# LHC.net
KiCad netlist of a schematic drawn in Altium Designer
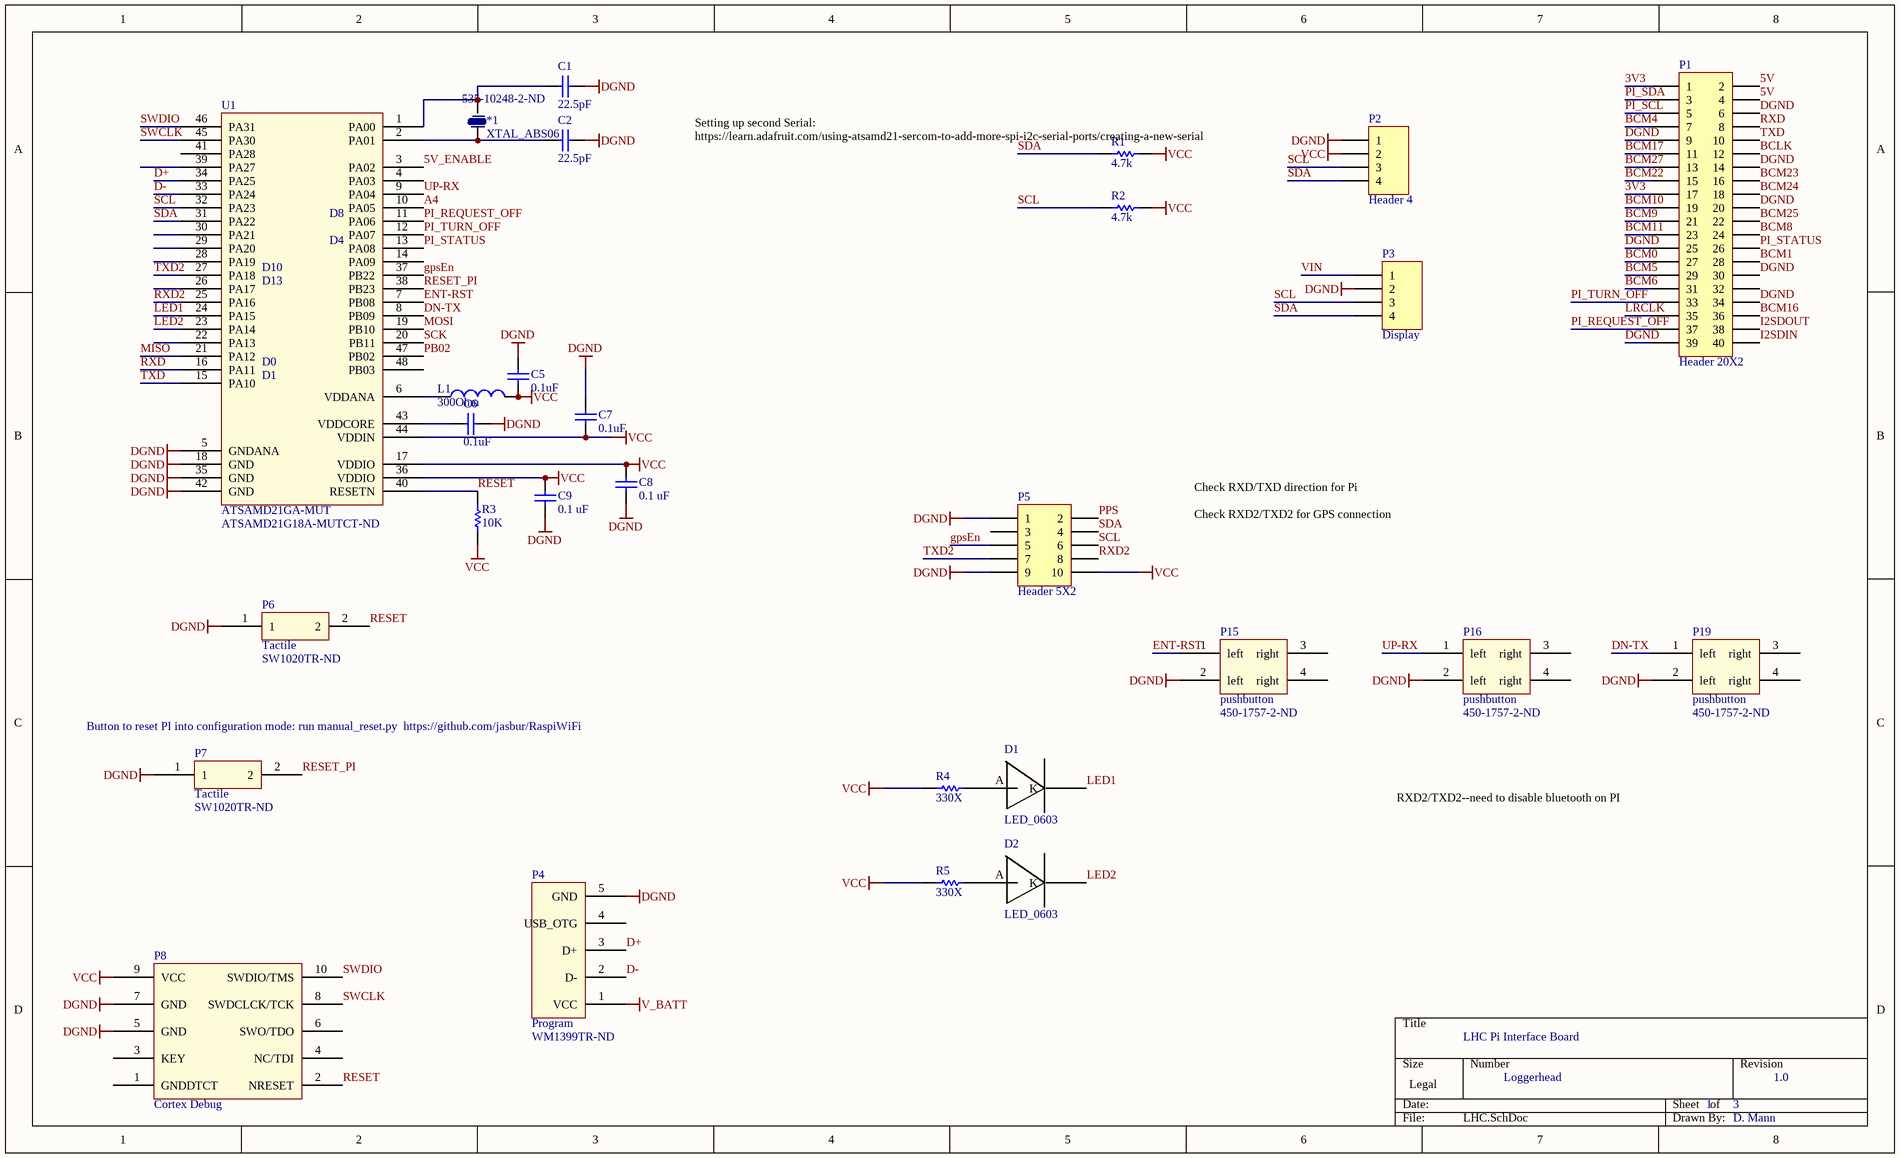
[diagram p0: LHC.SchDoc]

(export (version "E")
  (design (tool "Eeschema 10.0.6"))
  (components
    (comp (ref "*1")
      (value "XTAL_ABS06")
      (footprint "XTAL-ABS06")
      (fields (field (name "SUPPLIER PART NUMBER 1") "535-10248-2-ND"))
      (libsource (lib "Loggerhead") (part "XTAL_ABS06"))
    )
    (comp (ref "C1")
      (value "22.5pF")
      (footprint "0402")
      (description "Ceramic Chip Capacitor - Standard")
      (fields (field (name "PUBLISHER") "Altium Limited"))
      (libsource (lib "KEMET Chip Capacitor") (part "C0402"))
    )
    (comp (ref "C2")
      (value "22.5pF")
      (footprint "0402")
      (description "Ceramic Chip Capacitor - Standard")
      (fields (field (name "PUBLISHER") "Altium Limited"))
      (libsource (lib "KEMET Chip Capacitor") (part "C0402"))
    )
    (comp (ref "C5")
      (value "0.1uF")
      (footprint "0402")
      (description "Ceramic Chip Capacitor - Standard")
      (fields (field (name "PUBLISHER") "Altium Limited"))
      (libsource (lib "KEMET Chip Capacitor") (part "C0402"))
    )
    (comp (ref "C6")
      (value "0.1uF")
      (footprint "0402")
      (description "Ceramic Chip Capacitor - Standard")
      (fields (field (name "PUBLISHER") "Altium Limited"))
      (libsource (lib "KEMET Chip Capacitor") (part "C0402"))
    )
    (comp (ref "C7")
      (value "0.1uF")
      (footprint "0402")
      (description "Ceramic Chip Capacitor - Standard")
      (fields (field (name "PUBLISHER") "Altium Limited"))
      (libsource (lib "KEMET Chip Capacitor") (part "C0402"))
    )
    (comp (ref "C8")
      (value "0.1 uF")
      (footprint "0402")
      (description "Ceramic Chip Capacitor - Standard")
      (fields (field (name "PUBLISHER") "Altium Limited"))
      (libsource (lib "KEMET Chip Capacitor") (part "C0402"))
    )
    (comp (ref "C9")
      (value "0.1 uF")
      (footprint "0402")
      (description "Ceramic Chip Capacitor - Standard")
      (fields (field (name "PUBLISHER") "Altium Limited"))
      (libsource (lib "KEMET Chip Capacitor") (part "C0402"))
    )
    (comp (ref "D1")
      (value "LED_0603")
      (footprint "Diode0603")
      (libsource (lib "Loggerhead") (part "LED_0603"))
    )
    (comp (ref "D2")
      (value "LED_0603")
      (footprint "Diode0603")
      (libsource (lib "Loggerhead") (part "LED_0603"))
    )
    (comp (ref "L1")
      (value "300Ohm")
      (footprint "0805 (M2125) Ferrite")
      (description "Ferrite 25mOhm@DC,  60 Ohm@100MHz")
      (fields
        (field (name "CREATOR AND DATE") "Design Engineer's Name")
        (field (name "FOOTPRINT VERIFIED BY") "*")
        (field (name "SCHEMATIC VERIFIED BY") "*")
        (field (name "VENDOR INFO VERIFIED BY") "*")
      )
      (libsource (lib "Flanery") (part "Ferrite 0805(M2125) 3A"))
    )
    (comp (ref "P1")
      (value "Header 20X2")
      (footprint "HDR2X20")
      (description "Header, 20-Pin, Dual row")
      (fields (field (name "PUBLISHER") "Altium Limited"))
      (libsource (lib "Miscellaneous Connectors") (part "Header 20X2"))
    )
    (comp (ref "P2")
      (value "Header 4")
      (footprint "HDR1X4")
      (description "Header, 4-Pin")
      (fields (field (name "PUBLISHER") "Altium Limited"))
      (libsource (lib "Miscellaneous Connectors") (part "Header 4"))
    )
    (comp (ref "P3")
      (value "Display")
      (footprint "HDR1X4")
      (description "Header, 4-Pin")
      (fields (field (name "PUBLISHER") "Altium Limited"))
      (libsource (lib "Miscellaneous Connectors") (part "Header 4"))
    )
    (comp (ref "P4")
      (value "Program")
      (footprint "microUSB-B")
      (fields (field (name "SUPPLIER PART NUMBER 1") "WM1399TR-ND"))
      (libsource (lib "Loggerhead") (part "microUSB-B"))
    )
    (comp (ref "P5")
      (value "Header 5X2")
      (footprint "HDR2X5")
      (description "Header, 5-Pin, Dual row")
      (fields (field (name "PUBLISHER") "Altium Limited"))
      (libsource (lib "Miscellaneous Connectors") (part "Header 5X2"))
    )
    (comp (ref "P6")
      (value "Tactile")
      (footprint "Tactile-B3U-1000")
      (fields (field (name "SUPPLIER PART NUMBER 1") "SW1020TR-ND"))
      (libsource (lib "Loggerhead") (part "Tactile_B3U-1000"))
    )
    (comp (ref "P7")
      (value "Tactile")
      (footprint "Tactile-B3U-1000")
      (fields (field (name "SUPPLIER PART NUMBER 1") "SW1020TR-ND"))
      (libsource (lib "Loggerhead") (part "Tactile_B3U-1000"))
    )
    (comp (ref "P8")
      (value "Cortex Debug")
      (footprint "Header_2x5_50mil")
      (libsource (lib "Loggerhead") (part "CortexDebug"))
    )
    (comp (ref "P15")
      (value "pushbutton")
      (footprint "SOP4")
      (fields (field (name "SUPPLIER PART NUMBER 1") "450-1757-2-ND"))
      (libsource (lib "Loggerhead") (part "pushbutton"))
    )
    (comp (ref "P16")
      (value "pushbutton")
      (footprint "SOP4")
      (fields (field (name "SUPPLIER PART NUMBER 1") "450-1757-2-ND"))
      (libsource (lib "Loggerhead") (part "pushbutton"))
    )
    (comp (ref "P19")
      (value "pushbutton")
      (footprint "SOP4")
      (fields (field (name "SUPPLIER PART NUMBER 1") "450-1757-2-ND"))
      (libsource (lib "Loggerhead") (part "pushbutton"))
    )
    (comp (ref "R1")
      (value "4.7k")
      (footprint "3-0603")
      (fields (field (name "PUBLISHER") "Altium Limited"))
      (libsource (lib "Panasonic Resistor") (part "ERJ3RK"))
    )
    (comp (ref "R2")
      (value "4.7k")
      (footprint "3-0603")
      (fields (field (name "PUBLISHER") "Altium Limited"))
      (libsource (lib "Panasonic Resistor") (part "ERJ3RK"))
    )
    (comp (ref "R3")
      (value "10K")
      (footprint "3-0603")
      (fields (field (name "PUBLISHER") "Altium Limited"))
      (libsource (lib "Panasonic Resistor") (part "ERJ3RK"))
    )
    (comp (ref "R4")
      (value "330X")
      (footprint "3-0603")
      (fields (field (name "PUBLISHER") "Altium Limited"))
      (libsource (lib "Panasonic Resistor") (part "ERJ3RK"))
    )
    (comp (ref "R5")
      (value "330X")
      (footprint "3-0603")
      (fields (field (name "PUBLISHER") "Altium Limited"))
      (libsource (lib "Panasonic Resistor") (part "ERJ3RK"))
    )
    (comp (ref "U1")
      (value "ATSAMD21GA-MUT")
      (footprint "QFN127P600-8N")
      (fields (field (name "SUPPLIER PART NUMBER 1") "ATSAMD21G18A-MUTCT-ND"))
      (libsource (lib "Loggerhead") (part "ATSAMD21G18"))
    )
  )
  (nets
    (net (code "1") (name "/3V3") (class "Default")
      (node (ref "P1") (pin "1") (pinfunction "1_1") (pintype "passive"))
      (node (ref "P1") (pin "17") (pinfunction "17_17") (pintype "passive"))
    )
    (net (code "2") (name "/5V") (class "Default")
      (node (ref "P1") (pin "2") (pinfunction "2_2") (pintype "passive"))
      (node (ref "P1") (pin "4") (pinfunction "4_4") (pintype "passive"))
    )
    (net (code "3") (name "/5V_ENABLE") (class "Default")
      (node (ref "U1") (pin "3") (pinfunction "PA02_3") (pintype "passive"))
    )
    (net (code "4") (name "/A4") (class "Default")
      (node (ref "U1") (pin "10") (pinfunction "PA05_10") (pintype "passive"))
    )
    (net (code "5") (name "/BCLK") (class "Default")
      (node (ref "P1") (pin "12") (pinfunction "12_12") (pintype "passive"))
    )
    (net (code "6") (name "/BCM0") (class "Default")
      (node (ref "P1") (pin "27") (pinfunction "27_27") (pintype "passive"))
    )
    (net (code "7") (name "/BCM1") (class "Default")
      (node (ref "P1") (pin "28") (pinfunction "28_28") (pintype "passive"))
    )
    (net (code "8") (name "/BCM4") (class "Default")
      (node (ref "P1") (pin "7") (pinfunction "7_7") (pintype "passive"))
    )
    (net (code "9") (name "/BCM5") (class "Default")
      (node (ref "P1") (pin "29") (pinfunction "29_29") (pintype "passive"))
    )
    (net (code "10") (name "/BCM6") (class "Default")
      (node (ref "P1") (pin "31") (pinfunction "31_31") (pintype "passive"))
    )
    (net (code "11") (name "/BCM8") (class "Default")
      (node (ref "P1") (pin "24") (pinfunction "24_24") (pintype "passive"))
    )
    (net (code "12") (name "/BCM9") (class "Default")
      (node (ref "P1") (pin "21") (pinfunction "21_21") (pintype "passive"))
    )
    (net (code "13") (name "/BCM10") (class "Default")
      (node (ref "P1") (pin "19") (pinfunction "19_19") (pintype "passive"))
    )
    (net (code "14") (name "/BCM11") (class "Default")
      (node (ref "P1") (pin "23") (pinfunction "23_23") (pintype "passive"))
    )
    (net (code "15") (name "/BCM16") (class "Default")
      (node (ref "P1") (pin "36") (pinfunction "36_36") (pintype "passive"))
    )
    (net (code "16") (name "/BCM17") (class "Default")
      (node (ref "P1") (pin "11") (pinfunction "11_11") (pintype "passive"))
    )
    (net (code "17") (name "/BCM22") (class "Default")
      (node (ref "P1") (pin "15") (pinfunction "15_15") (pintype "passive"))
    )
    (net (code "18") (name "/BCM23") (class "Default")
      (node (ref "P1") (pin "16") (pinfunction "16_16") (pintype "passive"))
    )
    (net (code "19") (name "/BCM24") (class "Default")
      (node (ref "P1") (pin "18") (pinfunction "18_18") (pintype "passive"))
    )
    (net (code "20") (name "/BCM25") (class "Default")
      (node (ref "P1") (pin "22") (pinfunction "22_22") (pintype "passive"))
    )
    (net (code "21") (name "/BCM27") (class "Default")
      (node (ref "P1") (pin "13") (pinfunction "13_13") (pintype "passive"))
    )
    (net (code "22") (name "/D+") (class "Default")
      (node (ref "P4") (pin "3") (pinfunction "D+_3") (pintype "passive"))
      (node (ref "U1") (pin "34") (pinfunction "PA25_34") (pintype "passive"))
    )
    (net (code "23") (name "/D-") (class "Default")
      (node (ref "P4") (pin "2") (pinfunction "D-_2") (pintype "passive"))
      (node (ref "U1") (pin "33") (pinfunction "PA24_33") (pintype "passive"))
    )
    (net (code "24") (name "/DN-TX") (class "Default")
      (node (ref "P19") (pin "1") (pinfunction "left_1") (pintype "passive"))
      (node (ref "U1") (pin "8") (pinfunction "PB09_8") (pintype "passive"))
    )
    (net (code "25") (name "/ENT-RST") (class "Default")
      (node (ref "P15") (pin "1") (pinfunction "left_1") (pintype "passive"))
      (node (ref "U1") (pin "7") (pinfunction "PB08_7") (pintype "passive"))
    )
    (net (code "26") (name "/I2SDIN") (class "Default")
      (node (ref "P1") (pin "40") (pinfunction "40_40") (pintype "passive"))
    )
    (net (code "27") (name "/I2SDOUT") (class "Default")
      (node (ref "P1") (pin "38") (pinfunction "38_38") (pintype "passive"))
    )
    (net (code "28") (name "/LED1") (class "Default")
      (node (ref "D1") (pin "K") (pinfunction "K_K") (pintype "passive"))
      (node (ref "U1") (pin "24") (pinfunction "PA15_24") (pintype "passive"))
    )
    (net (code "29") (name "/LED2") (class "Default")
      (node (ref "D2") (pin "K") (pinfunction "K_K") (pintype "passive"))
      (node (ref "U1") (pin "23") (pinfunction "PA14_23") (pintype "passive"))
    )
    (net (code "30") (name "/LRCLK") (class "Default")
      (node (ref "P1") (pin "35") (pinfunction "35_35") (pintype "passive"))
    )
    (net (code "31") (name "/MISO") (class "Default")
      (node (ref "U1") (pin "21") (pinfunction "PA12_21") (pintype "passive"))
    )
    (net (code "32") (name "/MOSI") (class "Default")
      (node (ref "U1") (pin "19") (pinfunction "PB10_19") (pintype "passive"))
    )
    (net (code "33") (name "/PB02") (class "Default")
      (node (ref "U1") (pin "47") (pinfunction "PB02_47") (pintype "passive"))
    )
    (net (code "34") (name "/PI_REQUEST_OFF") (class "Default")
      (node (ref "P1") (pin "37") (pinfunction "37_37") (pintype "passive"))
      (node (ref "U1") (pin "11") (pinfunction "PA06_11") (pintype "passive"))
    )
    (net (code "35") (name "/PI_SCL") (class "Default")
      (node (ref "P1") (pin "5") (pinfunction "5_5") (pintype "passive"))
    )
    (net (code "36") (name "/PI_SDA") (class "Default")
      (node (ref "P1") (pin "3") (pinfunction "3_3") (pintype "passive"))
    )
    (net (code "37") (name "/PI_STATUS") (class "Default")
      (node (ref "P1") (pin "26") (pinfunction "26_26") (pintype "passive"))
      (node (ref "U1") (pin "13") (pinfunction "PA08_13") (pintype "passive"))
    )
    (net (code "38") (name "/PI_TURN_OFF") (class "Default")
      (node (ref "P1") (pin "33") (pinfunction "33_33") (pintype "passive"))
      (node (ref "U1") (pin "12") (pinfunction "PA07_12") (pintype "passive"))
    )
    (net (code "39") (name "/PPS") (class "Default")
      (node (ref "P5") (pin "2") (pinfunction "2_2") (pintype "passive"))
    )
    (net (code "40") (name "/RESET") (class "Default")
      (node (ref "P6") (pin "2") (pinfunction "2_2") (pintype "passive"))
      (node (ref "P8") (pin "2") (pinfunction "NRESET_2") (pintype "passive"))
      (node (ref "R3") (pin "2") (pinfunction "2_2") (pintype "passive"))
      (node (ref "U1") (pin "40") (pinfunction "RESETN_40") (pintype "passive"))
    )
    (net (code "41") (name "/RESET_PI") (class "Default")
      (node (ref "P7") (pin "2") (pinfunction "2_2") (pintype "passive"))
      (node (ref "U1") (pin "38") (pinfunction "PB23_38") (pintype "passive"))
    )
    (net (code "42") (name "/RXD") (class "Default")
      (node (ref "P1") (pin "8") (pinfunction "8_8") (pintype "passive"))
      (node (ref "U1") (pin "16") (pinfunction "PA11_16") (pintype "passive"))
    )
    (net (code "43") (name "/RXD2") (class "Default")
      (node (ref "P5") (pin "8") (pinfunction "8_8") (pintype "passive"))
      (node (ref "U1") (pin "25") (pinfunction "PA16_25") (pintype "passive"))
    )
    (net (code "44") (name "/SCK") (class "Default")
      (node (ref "U1") (pin "20") (pinfunction "PB11_20") (pintype "passive"))
    )
    (net (code "45") (name "/SCL") (class "Default")
      (node (ref "P2") (pin "3") (pinfunction "3_3") (pintype "passive"))
      (node (ref "P3") (pin "3") (pinfunction "3_3") (pintype "passive"))
      (node (ref "P5") (pin "6") (pinfunction "6_6") (pintype "passive"))
      (node (ref "R2") (pin "1") (pinfunction "1_1") (pintype "passive"))
      (node (ref "U1") (pin "32") (pinfunction "PA23_32") (pintype "passive"))
    )
    (net (code "46") (name "/SDA") (class "Default")
      (node (ref "P2") (pin "4") (pinfunction "4_4") (pintype "passive"))
      (node (ref "P3") (pin "4") (pinfunction "4_4") (pintype "passive"))
      (node (ref "P5") (pin "4") (pinfunction "4_4") (pintype "passive"))
      (node (ref "R1") (pin "1") (pinfunction "1_1") (pintype "passive"))
      (node (ref "U1") (pin "31") (pinfunction "PA22_31") (pintype "passive"))
    )
    (net (code "47") (name "/SWCLK") (class "Default")
      (node (ref "P8") (pin "8") (pinfunction "SWDCLCK/TCK_8") (pintype "passive"))
      (node (ref "U1") (pin "45") (pinfunction "PA30_45") (pintype "passive"))
    )
    (net (code "48") (name "/SWDIO") (class "Default")
      (node (ref "P8") (pin "10") (pinfunction "SWDIO/TMS_10") (pintype "passive"))
      (node (ref "U1") (pin "46") (pinfunction "PA31_46") (pintype "passive"))
    )
    (net (code "49") (name "/TXD") (class "Default")
      (node (ref "P1") (pin "10") (pinfunction "10_10") (pintype "passive"))
      (node (ref "U1") (pin "15") (pinfunction "PA10_15") (pintype "passive"))
    )
    (net (code "50") (name "/TXD2") (class "Default")
      (node (ref "P5") (pin "7") (pinfunction "7_7") (pintype "passive"))
      (node (ref "U1") (pin "27") (pinfunction "PA18_27") (pintype "passive"))
    )
    (net (code "51") (name "/UP-RX") (class "Default")
      (node (ref "P16") (pin "1") (pinfunction "left_1") (pintype "passive"))
      (node (ref "U1") (pin "9") (pinfunction "PA04_9") (pintype "passive"))
    )
    (net (code "52") (name "/VIN") (class "Default")
      (node (ref "P3") (pin "1") (pinfunction "1_1") (pintype "passive"))
    )
    (net (code "53") (name "/gpsEn") (class "Default")
      (node (ref "P5") (pin "5") (pinfunction "5_5") (pintype "passive"))
      (node (ref "U1") (pin "37") (pinfunction "PB22_37") (pintype "passive"))
    )
    (net (code "54") (name "DGND") (class "Default")
      (node (ref "C1") (pin "1") (pinfunction "1_1") (pintype "passive"))
      (node (ref "C2") (pin "1") (pinfunction "1_1") (pintype "passive"))
      (node (ref "C5") (pin "2") (pinfunction "2_2") (pintype "passive"))
      (node (ref "C6") (pin "2") (pinfunction "2_2") (pintype "passive"))
      (node (ref "C7") (pin "2") (pinfunction "2_2") (pintype "passive"))
      (node (ref "C8") (pin "2") (pinfunction "2_2") (pintype "passive"))
      (node (ref "C9") (pin "2") (pinfunction "2_2") (pintype "passive"))
      (node (ref "P1") (pin "14") (pinfunction "14_14") (pintype "passive"))
      (node (ref "P1") (pin "20") (pinfunction "20_20") (pintype "passive"))
      (node (ref "P1") (pin "25") (pinfunction "25_25") (pintype "passive"))
      (node (ref "P1") (pin "30") (pinfunction "30_30") (pintype "passive"))
      (node (ref "P1") (pin "34") (pinfunction "34_34") (pintype "passive"))
      (node (ref "P1") (pin "39") (pinfunction "39_39") (pintype "passive"))
      (node (ref "P1") (pin "6") (pinfunction "6_6") (pintype "passive"))
      (node (ref "P1") (pin "9") (pinfunction "9_9") (pintype "passive"))
      (node (ref "P15") (pin "2") (pinfunction "left_2") (pintype "passive"))
      (node (ref "P16") (pin "2") (pinfunction "left_2") (pintype "passive"))
      (node (ref "P19") (pin "2") (pinfunction "left_2") (pintype "passive"))
      (node (ref "P2") (pin "1") (pinfunction "1_1") (pintype "passive"))
      (node (ref "P3") (pin "2") (pinfunction "2_2") (pintype "passive"))
      (node (ref "P4") (pin "5") (pinfunction "GND_5") (pintype "passive"))
      (node (ref "P5") (pin "1") (pinfunction "1_1") (pintype "passive"))
      (node (ref "P5") (pin "9") (pinfunction "9_9") (pintype "passive"))
      (node (ref "P6") (pin "1") (pinfunction "1_1") (pintype "passive"))
      (node (ref "P7") (pin "1") (pinfunction "1_1") (pintype "passive"))
      (node (ref "P8") (pin "5") (pinfunction "GND_5") (pintype "passive"))
      (node (ref "P8") (pin "7") (pinfunction "GND_7") (pintype "passive"))
      (node (ref "U1") (pin "18") (pinfunction "GND_18") (pintype "passive"))
      (node (ref "U1") (pin "35") (pinfunction "GND_35") (pintype "passive"))
      (node (ref "U1") (pin "42") (pinfunction "GND_42") (pintype "passive"))
      (node (ref "U1") (pin "5") (pinfunction "GNDANA_5") (pintype "passive"))
    )
    (net (code "55") (name "Net-(D1-PadA)") (class "Default")
      (node (ref "D1") (pin "A") (pinfunction "A_A") (pintype "passive"))
      (node (ref "R4") (pin "2") (pinfunction "2_2") (pintype "passive"))
    )
    (net (code "56") (name "Net-(D2-PadA)") (class "Default")
      (node (ref "D2") (pin "A") (pinfunction "A_A") (pintype "passive"))
      (node (ref "R5") (pin "2") (pinfunction "2_2") (pintype "passive"))
    )
    (net (code "57") (name "Net-(U1-PA00)") (class "Default")
      (node (ref "*1") (pin "2") (pinfunction "2_2") (pintype "passive"))
      (node (ref "C1") (pin "2") (pinfunction "2_2") (pintype "passive"))
      (node (ref "U1") (pin "1") (pinfunction "PA00_1") (pintype "passive"))
    )
    (net (code "58") (name "Net-(U1-PA01)") (class "Default")
      (node (ref "*1") (pin "1") (pinfunction "1_1") (pintype "passive"))
      (node (ref "C2") (pin "2") (pinfunction "2_2") (pintype "passive"))
      (node (ref "U1") (pin "2") (pinfunction "PA01_2") (pintype "passive"))
    )
    (net (code "59") (name "Net-(U1-VDDANA)") (class "Default")
      (node (ref "L1") (pin "1") (pinfunction "1_1") (pintype "passive"))
      (node (ref "U1") (pin "6") (pinfunction "VDDANA_6") (pintype "passive"))
    )
    (net (code "60") (name "Net-(U1-VDDCORE)") (class "Default")
      (node (ref "C6") (pin "1") (pinfunction "1_1") (pintype "passive"))
      (node (ref "U1") (pin "43") (pinfunction "VDDCORE_43") (pintype "passive"))
    )
    (net (code "61") (name "VCC") (class "Default")
      (node (ref "C5") (pin "1") (pinfunction "1_1") (pintype "passive"))
      (node (ref "C7") (pin "1") (pinfunction "1_1") (pintype "passive"))
      (node (ref "C8") (pin "1") (pinfunction "1_1") (pintype "passive"))
      (node (ref "C9") (pin "1") (pinfunction "1_1") (pintype "passive"))
      (node (ref "L1") (pin "2") (pinfunction "2_2") (pintype "passive"))
      (node (ref "P2") (pin "2") (pinfunction "2_2") (pintype "passive"))
      (node (ref "P5") (pin "10") (pinfunction "10_10") (pintype "passive"))
      (node (ref "P8") (pin "9") (pinfunction "VCC_9") (pintype "passive"))
      (node (ref "R1") (pin "2") (pinfunction "2_2") (pintype "passive"))
      (node (ref "R2") (pin "2") (pinfunction "2_2") (pintype "passive"))
      (node (ref "R3") (pin "1") (pinfunction "1_1") (pintype "passive"))
      (node (ref "R4") (pin "1") (pinfunction "1_1") (pintype "passive"))
      (node (ref "R5") (pin "1") (pinfunction "1_1") (pintype "passive"))
      (node (ref "U1") (pin "17") (pinfunction "VDDIO_17") (pintype "passive"))
      (node (ref "U1") (pin "36") (pinfunction "VDDIO_36") (pintype "passive"))
      (node (ref "U1") (pin "44") (pinfunction "VDDIN_44") (pintype "passive"))
    )
    (net (code "62") (name "V_BATT") (class "Default")
      (node (ref "P4") (pin "1") (pinfunction "VCC_1") (pintype "passive"))
    )
    (net (code "63") (name "unconnected-(P1-Pad32)") (class "Default")
      (node (ref "P1") (pin "32") (pinfunction "32_32") (pintype "passive"))
    )
    (net (code "64") (name "unconnected-(P4-USB_OTG-Pad4)") (class "Default")
      (node (ref "P4") (pin "4") (pinfunction "USB_OTG_4") (pintype "passive"))
    )
    (net (code "65") (name "unconnected-(P5-Pad3)") (class "Default")
      (node (ref "P5") (pin "3") (pinfunction "3_3") (pintype "passive"))
    )
    (net (code "66") (name "unconnected-(P8-GNDDTCT-Pad1)") (class "Default")
      (node (ref "P8") (pin "1") (pinfunction "GNDDTCT_1") (pintype "passive"))
    )
    (net (code "67") (name "unconnected-(P8-KEY-Pad3)") (class "Default")
      (node (ref "P8") (pin "3") (pinfunction "KEY_3") (pintype "passive"))
    )
    (net (code "68") (name "unconnected-(P8-NC{slash}TDI-Pad4)") (class "Default")
      (node (ref "P8") (pin "4") (pinfunction "NC/TDI_4") (pintype "passive"))
    )
    (net (code "69") (name "unconnected-(P8-SWO{slash}TDO-Pad6)") (class "Default")
      (node (ref "P8") (pin "6") (pinfunction "SWO/TDO_6") (pintype "passive"))
    )
    (net (code "70") (name "unconnected-(P15-right-Pad3)") (class "Default")
      (node (ref "P15") (pin "3") (pinfunction "right_3") (pintype "passive"))
    )
    (net (code "71") (name "unconnected-(P15-right-Pad4)") (class "Default")
      (node (ref "P15") (pin "4") (pinfunction "right_4") (pintype "passive"))
    )
    (net (code "72") (name "unconnected-(P16-right-Pad3)") (class "Default")
      (node (ref "P16") (pin "3") (pinfunction "right_3") (pintype "passive"))
    )
    (net (code "73") (name "unconnected-(P16-right-Pad4)") (class "Default")
      (node (ref "P16") (pin "4") (pinfunction "right_4") (pintype "passive"))
    )
    (net (code "74") (name "unconnected-(P19-right-Pad3)") (class "Default")
      (node (ref "P19") (pin "3") (pinfunction "right_3") (pintype "passive"))
    )
    (net (code "75") (name "unconnected-(P19-right-Pad4)") (class "Default")
      (node (ref "P19") (pin "4") (pinfunction "right_4") (pintype "passive"))
    )
    (net (code "76") (name "unconnected-(U1-PA03-Pad4)") (class "Default")
      (node (ref "U1") (pin "4") (pinfunction "PA03_4") (pintype "passive"))
    )
    (net (code "77") (name "unconnected-(U1-PA09-Pad14)") (class "Default")
      (node (ref "U1") (pin "14") (pinfunction "PA09_14") (pintype "passive"))
    )
    (net (code "78") (name "unconnected-(U1-PA13-Pad22)") (class "Default")
      (node (ref "U1") (pin "22") (pinfunction "PA13_22") (pintype "passive"))
    )
    (net (code "79") (name "unconnected-(U1-PA17-Pad26)") (class "Default")
      (node (ref "U1") (pin "26") (pinfunction "PA17_26") (pintype "passive"))
    )
    (net (code "80") (name "unconnected-(U1-PA19-Pad28)") (class "Default")
      (node (ref "U1") (pin "28") (pinfunction "PA19_28") (pintype "passive"))
    )
    (net (code "81") (name "unconnected-(U1-PA20-Pad29)") (class "Default")
      (node (ref "U1") (pin "29") (pinfunction "PA20_29") (pintype "passive"))
    )
    (net (code "82") (name "unconnected-(U1-PA21-Pad30)") (class "Default")
      (node (ref "U1") (pin "30") (pinfunction "PA21_30") (pintype "passive"))
    )
    (net (code "83") (name "unconnected-(U1-PA27-Pad39)") (class "Default")
      (node (ref "U1") (pin "39") (pinfunction "PA27_39") (pintype "passive"))
    )
    (net (code "84") (name "unconnected-(U1-PA28-Pad41)") (class "Default")
      (node (ref "U1") (pin "41") (pinfunction "PA28_41") (pintype "passive"))
    )
    (net (code "85") (name "unconnected-(U1-PB03-Pad48)") (class "Default")
      (node (ref "U1") (pin "48") (pinfunction "PB03_48") (pintype "passive"))
    )
  )
)
